# Sheet1.net
KiCad netlist of a schematic drawn in Altium Designer
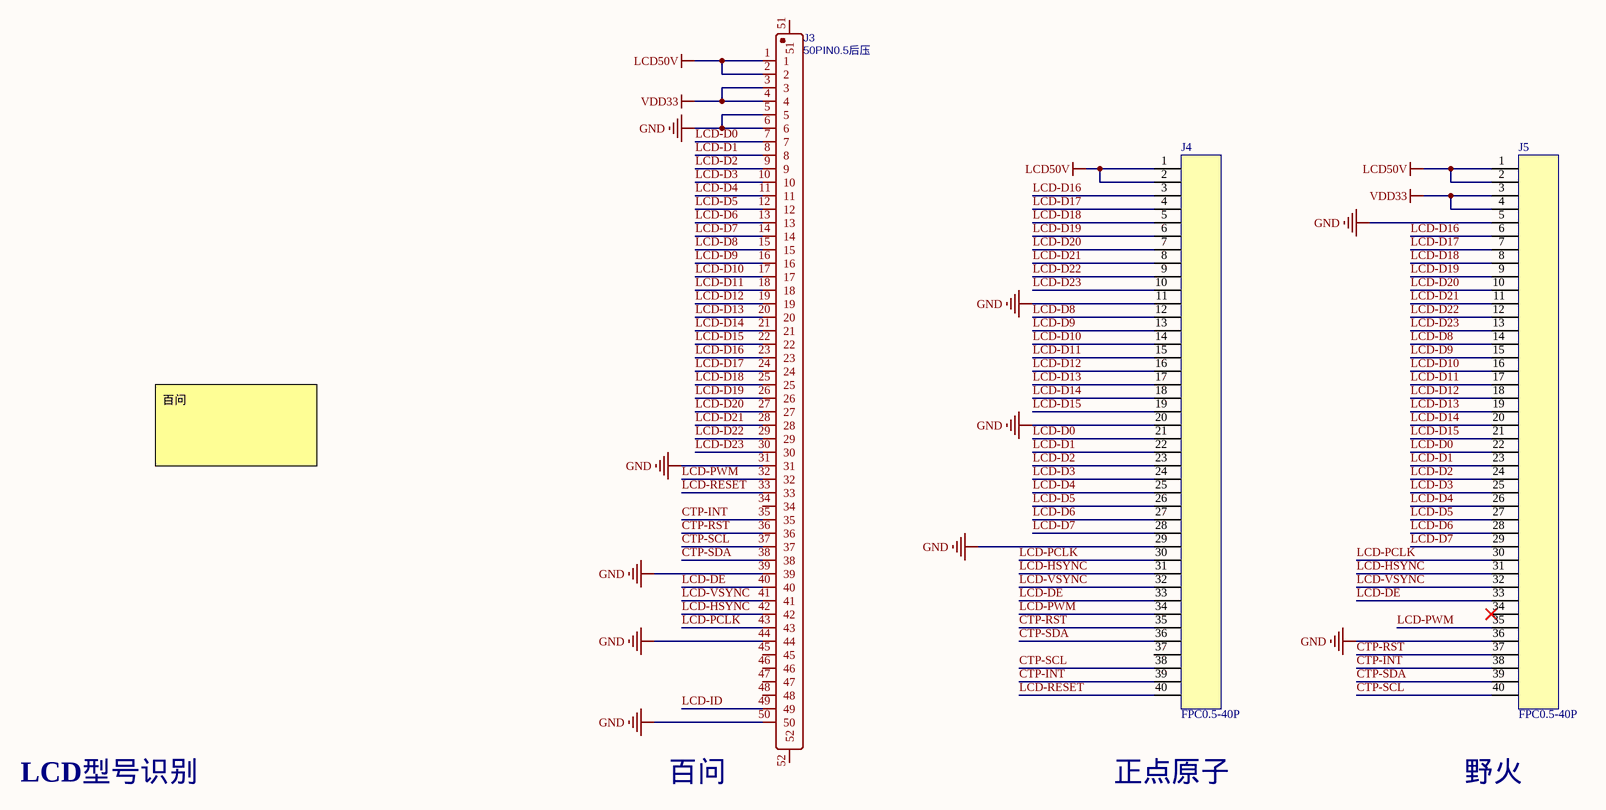
[diagram p0: Sheet1.SchDoc]

(export (version "E")
  (design (tool "Eeschema 10.0.6"))
  (components
    (comp (ref "J3")
      (value "50PIN0.5后压")
      (footprint "FPC-SMD_KH-FG0.5-H2.0-50PIN")
      (fields (field (name "BOM_SUPPLIER PART") "C9900011403") (field (name "CONTRIBUTOR") "LCSC"))
      (libsource (lib "altium-import") (part "root_0_50PIN0.5后压_"))
    )
    (comp (ref "J4")
      (value "FPC0.5-40P")
      (footprint "FPC0.5-40P")
      (description "贴片")
      (libsource (lib "插接类-FPC") (part "FPC0.5-40P"))
    )
    (comp (ref "J5")
      (value "FPC0.5-40P")
      (footprint "FPC0.5-40P")
      (description "贴片")
      (libsource (lib "插接类-FPC") (part "FPC0.5-40P"))
    )
  )
  (nets
    (net (code "1") (name "/CTP-INT") (class "Default")
      (node (ref "J3") (pin "35") (pinfunction "35_35") (pintype "passive"))
      (node (ref "J4") (pin "39") (pinfunction "39_39") (pintype "passive"))
      (node (ref "J5") (pin "38") (pinfunction "38_38") (pintype "passive"))
    )
    (net (code "2") (name "/CTP-RST") (class "Default")
      (node (ref "J3") (pin "36") (pinfunction "36_36") (pintype "passive"))
      (node (ref "J4") (pin "35") (pinfunction "35_35") (pintype "passive"))
      (node (ref "J5") (pin "37") (pinfunction "37_37") (pintype "passive"))
    )
    (net (code "3") (name "/CTP-SCL") (class "Default")
      (node (ref "J3") (pin "37") (pinfunction "37_37") (pintype "passive"))
      (node (ref "J4") (pin "38") (pinfunction "38_38") (pintype "passive"))
      (node (ref "J5") (pin "40") (pinfunction "40_40") (pintype "passive"))
    )
    (net (code "4") (name "/CTP-SDA") (class "Default")
      (node (ref "J3") (pin "38") (pinfunction "38_38") (pintype "passive"))
      (node (ref "J4") (pin "36") (pinfunction "36_36") (pintype "passive"))
      (node (ref "J5") (pin "39") (pinfunction "39_39") (pintype "passive"))
    )
    (net (code "5") (name "/LCD-D0") (class "Default")
      (node (ref "J3") (pin "7") (pinfunction "7_7") (pintype "passive"))
      (node (ref "J4") (pin "21") (pinfunction "21_21") (pintype "passive"))
      (node (ref "J5") (pin "22") (pinfunction "22_22") (pintype "passive"))
    )
    (net (code "6") (name "/LCD-D1") (class "Default")
      (node (ref "J3") (pin "8") (pinfunction "8_8") (pintype "passive"))
      (node (ref "J4") (pin "22") (pinfunction "22_22") (pintype "passive"))
      (node (ref "J5") (pin "23") (pinfunction "23_23") (pintype "passive"))
    )
    (net (code "7") (name "/LCD-D2") (class "Default")
      (node (ref "J3") (pin "9") (pinfunction "9_9") (pintype "passive"))
      (node (ref "J4") (pin "23") (pinfunction "23_23") (pintype "passive"))
      (node (ref "J5") (pin "24") (pinfunction "24_24") (pintype "passive"))
    )
    (net (code "8") (name "/LCD-D3") (class "Default")
      (node (ref "J3") (pin "10") (pinfunction "10_10") (pintype "passive"))
      (node (ref "J4") (pin "24") (pinfunction "24_24") (pintype "passive"))
      (node (ref "J5") (pin "25") (pinfunction "25_25") (pintype "passive"))
    )
    (net (code "9") (name "/LCD-D4") (class "Default")
      (node (ref "J3") (pin "11") (pinfunction "11_11") (pintype "passive"))
      (node (ref "J4") (pin "25") (pinfunction "25_25") (pintype "passive"))
      (node (ref "J5") (pin "26") (pinfunction "26_26") (pintype "passive"))
    )
    (net (code "10") (name "/LCD-D5") (class "Default")
      (node (ref "J3") (pin "12") (pinfunction "12_12") (pintype "passive"))
      (node (ref "J4") (pin "26") (pinfunction "26_26") (pintype "passive"))
      (node (ref "J5") (pin "27") (pinfunction "27_27") (pintype "passive"))
    )
    (net (code "11") (name "/LCD-D6") (class "Default")
      (node (ref "J3") (pin "13") (pinfunction "13_13") (pintype "passive"))
      (node (ref "J4") (pin "27") (pinfunction "27_27") (pintype "passive"))
      (node (ref "J5") (pin "28") (pinfunction "28_28") (pintype "passive"))
    )
    (net (code "12") (name "/LCD-D7") (class "Default")
      (node (ref "J3") (pin "14") (pinfunction "14_14") (pintype "passive"))
      (node (ref "J4") (pin "28") (pinfunction "28_28") (pintype "passive"))
      (node (ref "J5") (pin "29") (pinfunction "29_29") (pintype "passive"))
    )
    (net (code "13") (name "/LCD-D8") (class "Default")
      (node (ref "J3") (pin "15") (pinfunction "15_15") (pintype "passive"))
      (node (ref "J4") (pin "12") (pinfunction "12_12") (pintype "passive"))
      (node (ref "J5") (pin "14") (pinfunction "14_14") (pintype "passive"))
    )
    (net (code "14") (name "/LCD-D9") (class "Default")
      (node (ref "J3") (pin "16") (pinfunction "16_16") (pintype "passive"))
      (node (ref "J4") (pin "13") (pinfunction "13_13") (pintype "passive"))
      (node (ref "J5") (pin "15") (pinfunction "15_15") (pintype "passive"))
    )
    (net (code "15") (name "/LCD-D10") (class "Default")
      (node (ref "J3") (pin "17") (pinfunction "17_17") (pintype "passive"))
      (node (ref "J4") (pin "14") (pinfunction "14_14") (pintype "passive"))
      (node (ref "J5") (pin "16") (pinfunction "16_16") (pintype "passive"))
    )
    (net (code "16") (name "/LCD-D11") (class "Default")
      (node (ref "J3") (pin "18") (pinfunction "18_18") (pintype "passive"))
      (node (ref "J4") (pin "15") (pinfunction "15_15") (pintype "passive"))
      (node (ref "J5") (pin "17") (pinfunction "17_17") (pintype "passive"))
    )
    (net (code "17") (name "/LCD-D12") (class "Default")
      (node (ref "J3") (pin "19") (pinfunction "19_19") (pintype "passive"))
      (node (ref "J4") (pin "16") (pinfunction "16_16") (pintype "passive"))
      (node (ref "J5") (pin "18") (pinfunction "18_18") (pintype "passive"))
    )
    (net (code "18") (name "/LCD-D13") (class "Default")
      (node (ref "J3") (pin "20") (pinfunction "20_20") (pintype "passive"))
      (node (ref "J4") (pin "17") (pinfunction "17_17") (pintype "passive"))
      (node (ref "J5") (pin "19") (pinfunction "19_19") (pintype "passive"))
    )
    (net (code "19") (name "/LCD-D14") (class "Default")
      (node (ref "J3") (pin "21") (pinfunction "21_21") (pintype "passive"))
      (node (ref "J4") (pin "18") (pinfunction "18_18") (pintype "passive"))
      (node (ref "J5") (pin "20") (pinfunction "20_20") (pintype "passive"))
    )
    (net (code "20") (name "/LCD-D15") (class "Default")
      (node (ref "J3") (pin "22") (pinfunction "22_22") (pintype "passive"))
      (node (ref "J4") (pin "19") (pinfunction "19_19") (pintype "passive"))
      (node (ref "J5") (pin "21") (pinfunction "21_21") (pintype "passive"))
    )
    (net (code "21") (name "/LCD-D16") (class "Default")
      (node (ref "J3") (pin "23") (pinfunction "23_23") (pintype "passive"))
      (node (ref "J4") (pin "3") (pinfunction "3_3") (pintype "passive"))
      (node (ref "J5") (pin "6") (pinfunction "6_6") (pintype "passive"))
    )
    (net (code "22") (name "/LCD-D17") (class "Default")
      (node (ref "J3") (pin "24") (pinfunction "24_24") (pintype "passive"))
      (node (ref "J4") (pin "4") (pinfunction "4_4") (pintype "passive"))
      (node (ref "J5") (pin "7") (pinfunction "7_7") (pintype "passive"))
    )
    (net (code "23") (name "/LCD-D18") (class "Default")
      (node (ref "J3") (pin "25") (pinfunction "25_25") (pintype "passive"))
      (node (ref "J4") (pin "5") (pinfunction "5_5") (pintype "passive"))
      (node (ref "J5") (pin "8") (pinfunction "8_8") (pintype "passive"))
    )
    (net (code "24") (name "/LCD-D19") (class "Default")
      (node (ref "J3") (pin "26") (pinfunction "26_26") (pintype "passive"))
      (node (ref "J4") (pin "6") (pinfunction "6_6") (pintype "passive"))
      (node (ref "J5") (pin "9") (pinfunction "9_9") (pintype "passive"))
    )
    (net (code "25") (name "/LCD-D20") (class "Default")
      (node (ref "J3") (pin "27") (pinfunction "27_27") (pintype "passive"))
      (node (ref "J4") (pin "7") (pinfunction "7_7") (pintype "passive"))
      (node (ref "J5") (pin "10") (pinfunction "10_10") (pintype "passive"))
    )
    (net (code "26") (name "/LCD-D21") (class "Default")
      (node (ref "J3") (pin "28") (pinfunction "28_28") (pintype "passive"))
      (node (ref "J4") (pin "8") (pinfunction "8_8") (pintype "passive"))
      (node (ref "J5") (pin "11") (pinfunction "11_11") (pintype "passive"))
    )
    (net (code "27") (name "/LCD-D22") (class "Default")
      (node (ref "J3") (pin "29") (pinfunction "29_29") (pintype "passive"))
      (node (ref "J4") (pin "9") (pinfunction "9_9") (pintype "passive"))
      (node (ref "J5") (pin "12") (pinfunction "12_12") (pintype "passive"))
    )
    (net (code "28") (name "/LCD-D23") (class "Default")
      (node (ref "J3") (pin "30") (pinfunction "30_30") (pintype "passive"))
      (node (ref "J4") (pin "10") (pinfunction "10_10") (pintype "passive"))
      (node (ref "J5") (pin "13") (pinfunction "13_13") (pintype "passive"))
    )
    (net (code "29") (name "/LCD-DE") (class "Default")
      (node (ref "J3") (pin "40") (pinfunction "40_40") (pintype "passive"))
      (node (ref "J4") (pin "33") (pinfunction "33_33") (pintype "passive"))
      (node (ref "J5") (pin "33") (pinfunction "33_33") (pintype "passive"))
    )
    (net (code "30") (name "/LCD-HSYNC") (class "Default")
      (node (ref "J3") (pin "42") (pinfunction "42_42") (pintype "passive"))
      (node (ref "J4") (pin "31") (pinfunction "31_31") (pintype "passive"))
      (node (ref "J5") (pin "31") (pinfunction "31_31") (pintype "passive"))
    )
    (net (code "31") (name "/LCD-ID") (class "Default")
      (node (ref "J3") (pin "49") (pinfunction "49_49") (pintype "passive"))
    )
    (net (code "32") (name "/LCD-PCLK") (class "Default")
      (node (ref "J3") (pin "43") (pinfunction "43_43") (pintype "passive"))
      (node (ref "J4") (pin "30") (pinfunction "30_30") (pintype "passive"))
      (node (ref "J5") (pin "30") (pinfunction "30_30") (pintype "passive"))
    )
    (net (code "33") (name "/LCD-PWM") (class "Default")
      (node (ref "J3") (pin "32") (pinfunction "32_32") (pintype "passive"))
      (node (ref "J4") (pin "34") (pinfunction "34_34") (pintype "passive"))
      (node (ref "J5") (pin "35") (pinfunction "35_35") (pintype "passive"))
    )
    (net (code "34") (name "/LCD-RESET") (class "Default")
      (node (ref "J3") (pin "33") (pinfunction "33_33") (pintype "passive"))
      (node (ref "J4") (pin "40") (pinfunction "40_40") (pintype "passive"))
    )
    (net (code "35") (name "/LCD-VSYNC") (class "Default")
      (node (ref "J3") (pin "41") (pinfunction "41_41") (pintype "passive"))
      (node (ref "J4") (pin "32") (pinfunction "32_32") (pintype "passive"))
      (node (ref "J5") (pin "32") (pinfunction "32_32") (pintype "passive"))
    )
    (net (code "36") (name "GND") (class "Default")
      (node (ref "J3") (pin "31") (pinfunction "31_31") (pintype "passive"))
      (node (ref "J3") (pin "39") (pinfunction "39_39") (pintype "passive"))
      (node (ref "J3") (pin "44") (pinfunction "44_44") (pintype "passive"))
      (node (ref "J3") (pin "5") (pinfunction "5_5") (pintype "passive"))
      (node (ref "J3") (pin "50") (pinfunction "50_50") (pintype "passive"))
      (node (ref "J3") (pin "6") (pinfunction "6_6") (pintype "passive"))
      (node (ref "J4") (pin "11") (pinfunction "11_11") (pintype "passive"))
      (node (ref "J4") (pin "20") (pinfunction "20_20") (pintype "passive"))
      (node (ref "J4") (pin "29") (pinfunction "29_29") (pintype "passive"))
      (node (ref "J5") (pin "36") (pinfunction "36_36") (pintype "passive"))
      (node (ref "J5") (pin "5") (pinfunction "5_5") (pintype "passive"))
    )
    (net (code "37") (name "LCD50V") (class "Default")
      (node (ref "J3") (pin "1") (pinfunction "1_1") (pintype "passive"))
      (node (ref "J3") (pin "2") (pinfunction "2_2") (pintype "passive"))
      (node (ref "J4") (pin "1") (pinfunction "1_1") (pintype "passive"))
      (node (ref "J4") (pin "2") (pinfunction "2_2") (pintype "passive"))
      (node (ref "J5") (pin "1") (pinfunction "1_1") (pintype "passive"))
      (node (ref "J5") (pin "2") (pinfunction "2_2") (pintype "passive"))
    )
    (net (code "38") (name "VDD33") (class "Default")
      (node (ref "J3") (pin "3") (pinfunction "3_3") (pintype "passive"))
      (node (ref "J3") (pin "4") (pinfunction "4_4") (pintype "passive"))
      (node (ref "J5") (pin "3") (pinfunction "3_3") (pintype "passive"))
      (node (ref "J5") (pin "4") (pinfunction "4_4") (pintype "passive"))
    )
    (net (code "39") (name "unconnected-(J3-Pad34)") (class "Default")
      (node (ref "J3") (pin "34") (pinfunction "34_34") (pintype "passive"))
    )
    (net (code "40") (name "unconnected-(J3-Pad45)") (class "Default")
      (node (ref "J3") (pin "45") (pinfunction "45_45") (pintype "passive"))
    )
    (net (code "41") (name "unconnected-(J3-Pad46)") (class "Default")
      (node (ref "J3") (pin "46") (pinfunction "46_46") (pintype "passive"))
    )
    (net (code "42") (name "unconnected-(J3-Pad47)") (class "Default")
      (node (ref "J3") (pin "47") (pinfunction "47_47") (pintype "passive"))
    )
    (net (code "43") (name "unconnected-(J3-Pad48)") (class "Default")
      (node (ref "J3") (pin "48") (pinfunction "48_48") (pintype "passive"))
    )
    (net (code "44") (name "unconnected-(J3-Pad51)") (class "Default")
      (node (ref "J3") (pin "51") (pinfunction "51_51") (pintype "passive"))
    )
    (net (code "45") (name "unconnected-(J3-Pad52)") (class "Default")
      (node (ref "J3") (pin "52") (pinfunction "52_52") (pintype "passive"))
    )
    (net (code "46") (name "unconnected-(J4-Pad37)") (class "Default")
      (node (ref "J4") (pin "37") (pinfunction "37_37") (pintype "passive"))
    )
    (net (code "47") (name "unconnected-(J5-Pad34)") (class "Default")
      (node (ref "J5") (pin "34") (pinfunction "34_34") (pintype "passive+no_connect"))
    )
  )
)
